# SuiveurLigne7.net
KiCad netlist of a schematic drawn in Altium Designer
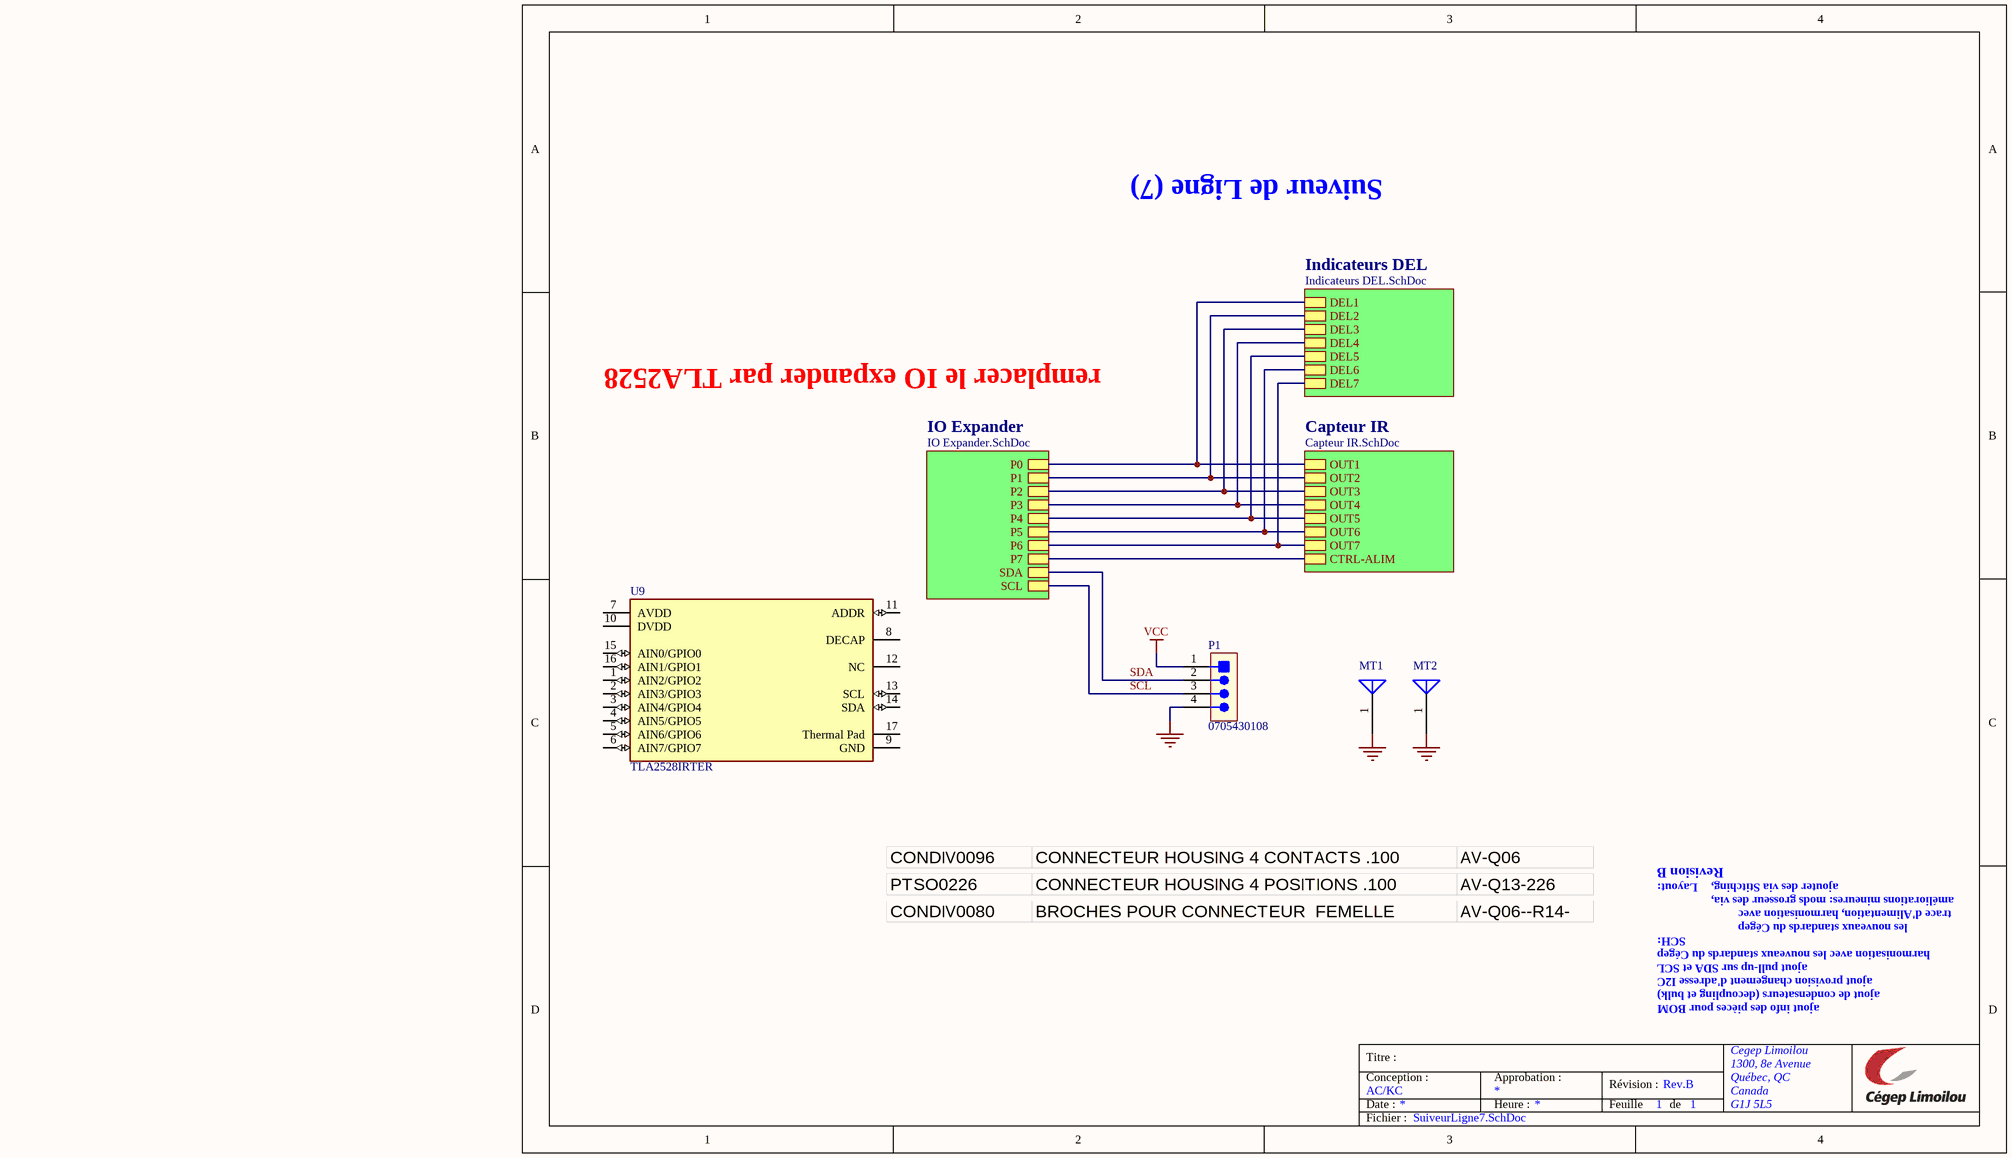
[diagram p0: SuiveurLigne7.SchDoc]

(export (version "E")
  (design (tool "Eeschema 10.0.6"))
  (components
    (comp (ref "MT1") (value "~") (footprint "MTHOLE") (libsource (lib "*") (part "ANTENNA")))
    (comp (ref "MT2") (value "~") (footprint "MTHOLE") (libsource (lib "*") (part "ANTENNA")))
    (comp (ref "P1")
      (value "0705430108")
      (footprint "MOLEX4")
      (description "CONN HEADER VERT 4POS 2.54MM")
      (libsource (lib "TEP-AltiumLib-Connectors") (part "CONN-100MIL-HDR-01X04-WIRE-TO-BORAD"))
    )
    (comp (ref "U9")
      (value "TLA2528IRTER")
      (footprint "FP-TLA2528IRTER-MFG")
      (description "SMALL 8-CHANNEL 12-BIT ANALOG-TO")
      (libsource (lib "Altium Content Vault") (part "aa31aa3499adeec6c9801c82924319d"))
    )
  )
  (nets
    (net (code "9") (name "/SCL") (class "Default")
      (node (ref "P1") (pin "3") (pinfunction "3_3") (pintype "passive"))
    )
    (net (code "10") (name "/SDA") (class "Default")
      (node (ref "P1") (pin "2") (pinfunction "2_2") (pintype "passive"))
    )
    (net (code "11") (name "GND") (class "Default")
      (node (ref "MT1") (pin "1") (pinfunction "1_1") (pintype "passive"))
      (node (ref "MT2") (pin "1") (pinfunction "1_1") (pintype "passive"))
      (node (ref "P1") (pin "4") (pinfunction "4_4") (pintype "passive"))
    )
    (net (code "12") (name "VCC") (class "Default")
      (node (ref "P1") (pin "1") (pinfunction "1_1") (pintype "passive"))
    )
    (net (code "13") (name "unconnected-(U9-ADDR-Pad11)") (class "Default")
      (node (ref "U9") (pin "11") (pinfunction "ADDR_11") (pintype "bidirectional"))
    )
    (net (code "14") (name "unconnected-(U9-AIN0{slash}GPIO0-Pad15)") (class "Default")
      (node (ref "U9") (pin "15") (pinfunction "AIN0/GPIO0_15") (pintype "bidirectional"))
    )
    (net (code "15") (name "unconnected-(U9-AIN1{slash}GPIO1-Pad16)") (class "Default")
      (node (ref "U9") (pin "16") (pinfunction "AIN1/GPIO1_16") (pintype "bidirectional"))
    )
    (net (code "16") (name "unconnected-(U9-AIN2{slash}GPIO2-Pad1)") (class "Default")
      (node (ref "U9") (pin "1") (pinfunction "AIN2/GPIO2_1") (pintype "bidirectional"))
    )
    (net (code "17") (name "unconnected-(U9-AIN3{slash}GPIO3-Pad2)") (class "Default")
      (node (ref "U9") (pin "2") (pinfunction "AIN3/GPIO3_2") (pintype "bidirectional"))
    )
    (net (code "18") (name "unconnected-(U9-AIN4{slash}GPIO4-Pad3)") (class "Default")
      (node (ref "U9") (pin "3") (pinfunction "AIN4/GPIO4_3") (pintype "bidirectional"))
    )
    (net (code "19") (name "unconnected-(U9-AIN5{slash}GPIO5-Pad4)") (class "Default")
      (node (ref "U9") (pin "4") (pinfunction "AIN5/GPIO5_4") (pintype "bidirectional"))
    )
    (net (code "20") (name "unconnected-(U9-AIN6{slash}GPIO6-Pad5)") (class "Default")
      (node (ref "U9") (pin "5") (pinfunction "AIN6/GPIO6_5") (pintype "bidirectional"))
    )
    (net (code "21") (name "unconnected-(U9-AIN7{slash}GPIO7-Pad6)") (class "Default")
      (node (ref "U9") (pin "6") (pinfunction "AIN7/GPIO7_6") (pintype "bidirectional"))
    )
    (net (code "22") (name "unconnected-(U9-AVDD-Pad7)") (class "Default")
      (node (ref "U9") (pin "7") (pinfunction "AVDD_7") (pintype "power_in"))
    )
    (net (code "23") (name "unconnected-(U9-DECAP-Pad8)") (class "Default")
      (node (ref "U9") (pin "8") (pinfunction "DECAP_8") (pintype "passive"))
    )
    (net (code "24") (name "unconnected-(U9-DVDD-Pad10)") (class "Default")
      (node (ref "U9") (pin "10") (pinfunction "DVDD_10") (pintype "power_in"))
    )
    (net (code "25") (name "unconnected-(U9-GND-Pad9)") (class "Default")
      (node (ref "U9") (pin "9") (pinfunction "GND_9") (pintype "power_in"))
    )
    (net (code "26") (name "unconnected-(U9-NC-Pad12)") (class "Default")
      (node (ref "U9") (pin "12") (pinfunction "NC_12") (pintype "passive"))
    )
    (net (code "27") (name "unconnected-(U9-SCL-Pad13)") (class "Default")
      (node (ref "U9") (pin "13") (pinfunction "SCL_13") (pintype "bidirectional"))
    )
    (net (code "28") (name "unconnected-(U9-SDA-Pad14)") (class "Default")
      (node (ref "U9") (pin "14") (pinfunction "SDA_14") (pintype "bidirectional"))
    )
    (net (code "29") (name "unconnected-(U9-Thermal_Pad-Pad17)") (class "Default")
      (node (ref "U9") (pin "17") (pinfunction "Thermal_Pad_17") (pintype "power_in"))
    )
  )
)
